# MRF24J40MA.net
KiCad netlist of a schematic drawn in Altium Designer
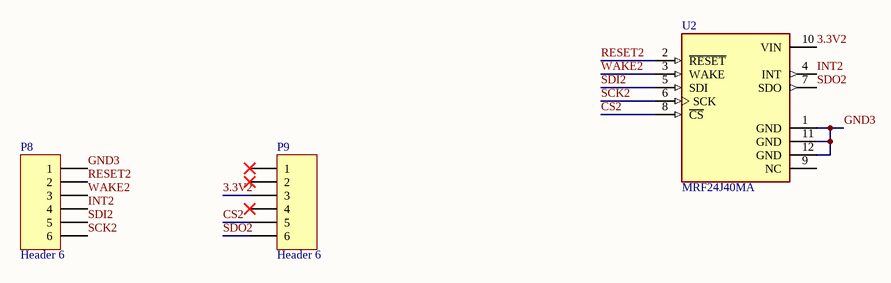
[diagram p0: MRF24J40MA.SchDoc]

(export (version "E")
  (design (tool "Eeschema 10.0.6"))
  (components
    (comp (ref "P8")
      (value "Header 6")
      (footprint "HDR1X6")
      (description "Header, 6-Pin")
      (fields (field (name "PUBLISHER") "Altium Limited"))
      (libsource (lib "Miscellaneous Connectors") (part "Header 6"))
    )
    (comp (ref "P9")
      (value "Header 6")
      (footprint "HDR1X6")
      (description "Header, 6-Pin")
      (fields (field (name "PUBLISHER") "Altium Limited"))
      (libsource (lib "") (part "Header 6_1"))
    )
    (comp (ref "U2")
      (value "MRF24J40MA")
      (footprint "MODULE_MRF24J40MA")
      (description "802.15.4 Zigbee Transceiver Module 2.4GHz Integrated, Trace Surface Mount")
      (fields (field (name "MF") "{'manufacturer': u'Microchip'}"))
      (libsource (lib "SnapEDA_Library") (part "MRF24J40MA"))
    )
  )
  (nets
    (net (code "1") (name "/3.3V2") (class "Default")
      (node (ref "P9") (pin "3") (pinfunction "3_3") (pintype "passive"))
      (node (ref "U2") (pin "10") (pinfunction "VIN_10") (pintype "power_in"))
    )
    (net (code "2") (name "/CS2") (class "Default")
      (node (ref "P9") (pin "5") (pinfunction "5_5") (pintype "passive"))
      (node (ref "U2") (pin "8") (pinfunction "~{CS}_8") (pintype "input"))
    )
    (net (code "3") (name "/GND3") (class "Default")
      (node (ref "P8") (pin "1") (pinfunction "1_1") (pintype "passive"))
      (node (ref "U2") (pin "1") (pinfunction "GND_1") (pintype "power_in"))
      (node (ref "U2") (pin "11") (pinfunction "GND_11") (pintype "power_in"))
      (node (ref "U2") (pin "12") (pinfunction "GND_12") (pintype "power_in"))
    )
    (net (code "4") (name "/INT2") (class "Default")
      (node (ref "P8") (pin "4") (pinfunction "4_4") (pintype "passive"))
      (node (ref "U2") (pin "4") (pinfunction "INT_4") (pintype "output"))
    )
    (net (code "5") (name "/RESET2") (class "Default")
      (node (ref "P8") (pin "2") (pinfunction "2_2") (pintype "passive"))
      (node (ref "U2") (pin "2") (pinfunction "~{RESET}_2") (pintype "input"))
    )
    (net (code "6") (name "/SCK2") (class "Default")
      (node (ref "P8") (pin "6") (pinfunction "6_6") (pintype "passive"))
      (node (ref "U2") (pin "6") (pinfunction "SCK_6") (pintype "input"))
    )
    (net (code "7") (name "/SDI2") (class "Default")
      (node (ref "P8") (pin "5") (pinfunction "5_5") (pintype "passive"))
      (node (ref "U2") (pin "5") (pinfunction "SDI_5") (pintype "input"))
    )
    (net (code "8") (name "/SDO2") (class "Default")
      (node (ref "P9") (pin "6") (pinfunction "6_6") (pintype "passive"))
      (node (ref "U2") (pin "7") (pinfunction "SDO_7") (pintype "output"))
    )
    (net (code "9") (name "/WAKE2") (class "Default")
      (node (ref "P8") (pin "3") (pinfunction "3_3") (pintype "passive"))
      (node (ref "U2") (pin "3") (pinfunction "WAKE_3") (pintype "input"))
    )
    (net (code "10") (name "unconnected-(P9-Pad1)") (class "Default")
      (node (ref "P9") (pin "1") (pinfunction "1_1") (pintype "passive+no_connect"))
    )
    (net (code "11") (name "unconnected-(P9-Pad2)") (class "Default")
      (node (ref "P9") (pin "2") (pinfunction "2_2") (pintype "passive+no_connect"))
    )
    (net (code "12") (name "unconnected-(P9-Pad4)") (class "Default")
      (node (ref "P9") (pin "4") (pinfunction "4_4") (pintype "passive+no_connect"))
    )
    (net (code "13") (name "unconnected-(U2-NC-Pad9)") (class "Default")
      (node (ref "U2") (pin "9") (pinfunction "NC_9") (pintype "passive"))
    )
  )
)
